# IotaWatt5_1.net
KiCad netlist of a schematic drawn in EAGLE
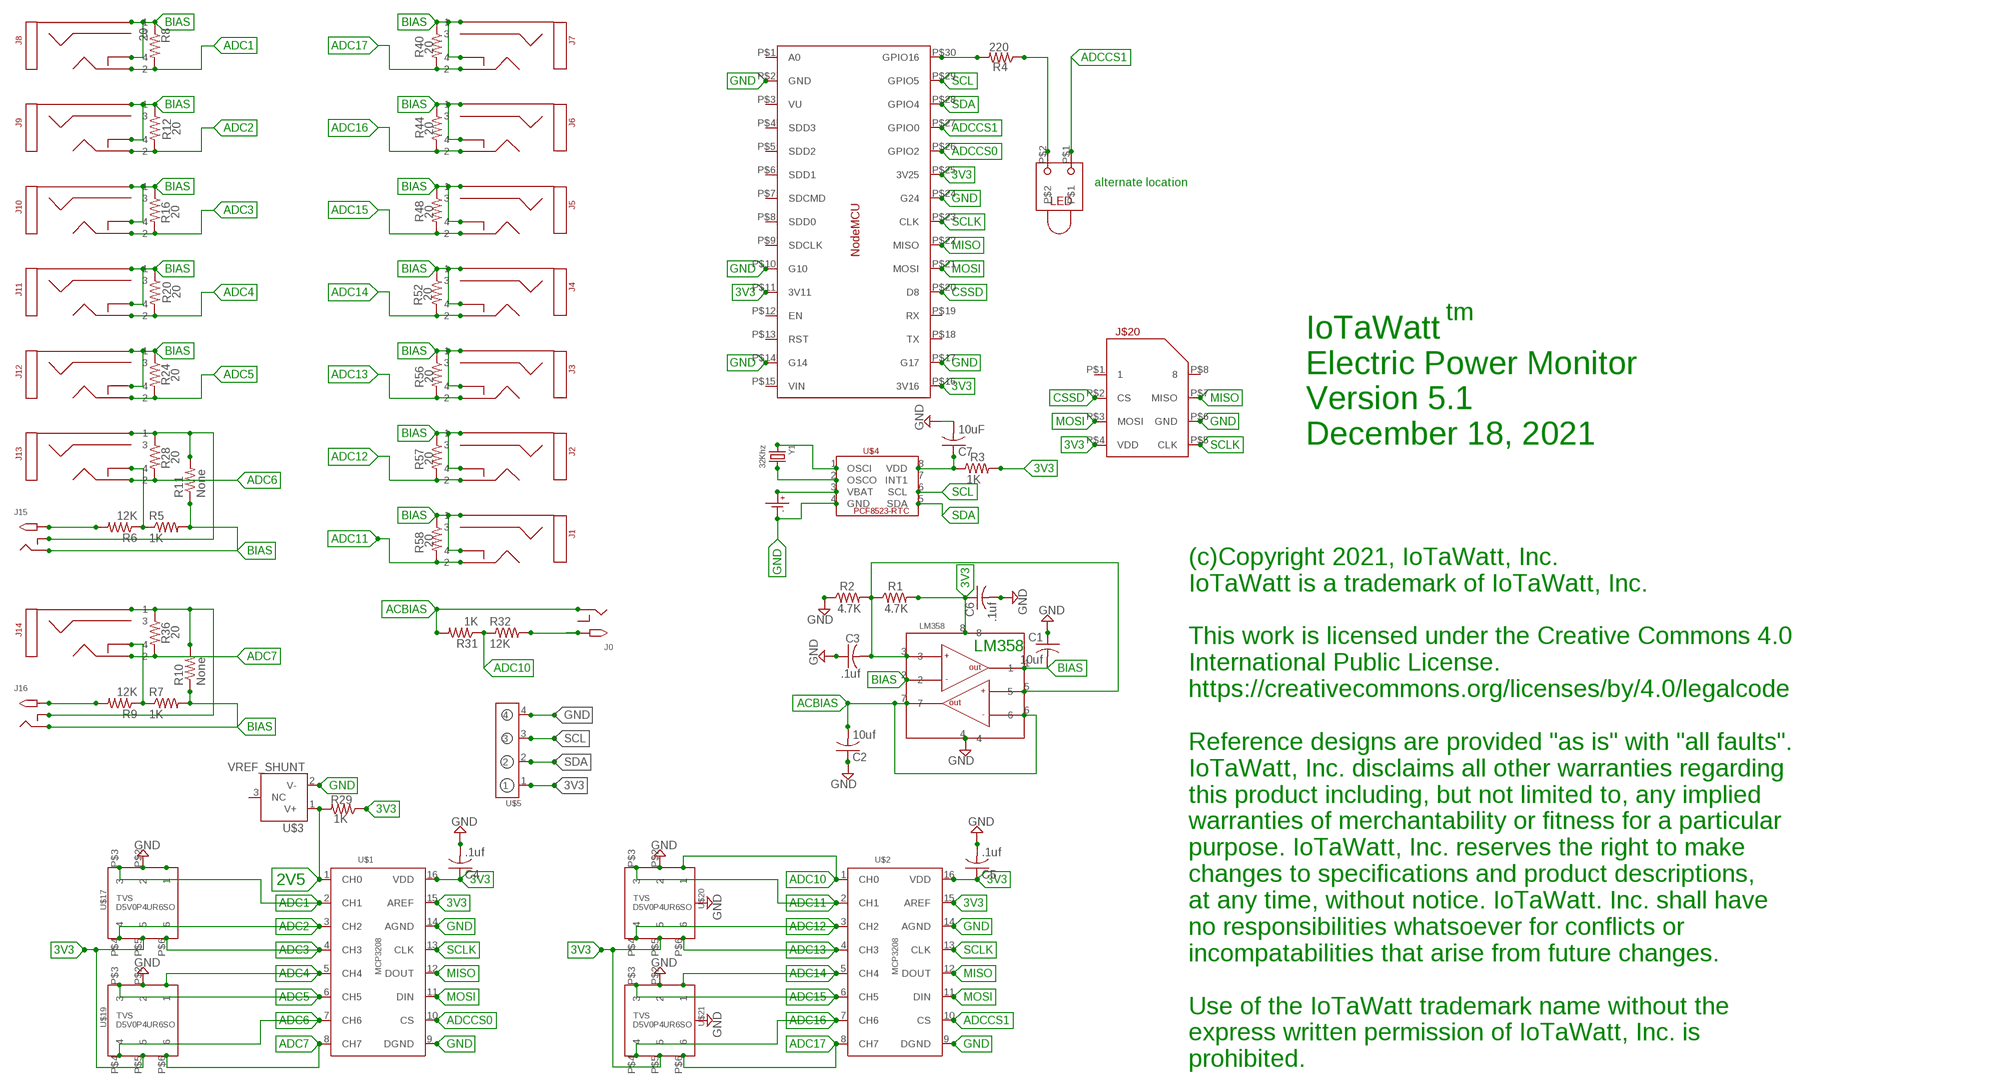
[diagram p0: schematic, sheet 1]

(export (version "E")
  (design (tool "Eeschema 10.0.6"))
  (components
    (comp (ref "C1")
      (value "10uf")
      (footprint "eagle-import:C0805")
      (libsource (lib "eagle-import") (part "C-USC0805"))
    )
    (comp (ref "C2")
      (value "10uf")
      (footprint "eagle-import:C0805")
      (libsource (lib "eagle-import") (part "C-USC0805"))
    )
    (comp (ref "C3")
      (value ".1uf")
      (footprint "eagle-import:C0805")
      (libsource (lib "eagle-import") (part "C-USC0805"))
    )
    (comp (ref "C4")
      (value ".1uf")
      (footprint "eagle-import:C0805")
      (libsource (lib "eagle-import") (part "C-USC0805"))
    )
    (comp (ref "C5")
      (value ".1uf")
      (footprint "eagle-import:C0805")
      (libsource (lib "eagle-import") (part "C-USC0805"))
    )
    (comp (ref "C6")
      (value ".1uf")
      (footprint "eagle-import:C0805")
      (libsource (lib "eagle-import") (part "C-USC0805"))
    )
    (comp (ref "C7")
      (value "10uF")
      (footprint "eagle-import:C0805")
      (libsource (lib "eagle-import") (part "C-USC0805"))
    )
    (comp (ref "J$20")
      (value "MICROSD_PUSH/PULL")
      (footprint "eagle-import:MICROSD")
      (libsource (lib "eagle-import") (part "MICROSD_PUSH/PULL"))
    )
    (comp (ref "J0")
      (value "2.1MMJACKSMT")
      (footprint "eagle-import:DCJACK_2MM_SMT")
      (libsource (lib "eagle-import") (part "2.1MMJACKSMT"))
    )
    (comp (ref "J1")
      (value "STEREO_SMD")
      (footprint "eagle-import:STEREO_SMT")
      (libsource (lib "eagle-import") (part "STEREO_SMD"))
    )
    (comp (ref "J2")
      (value "STEREO_SMD")
      (footprint "eagle-import:STEREO_SMT")
      (libsource (lib "eagle-import") (part "STEREO_SMD"))
    )
    (comp (ref "J3")
      (value "STEREO_SMD")
      (footprint "eagle-import:STEREO_SMT")
      (libsource (lib "eagle-import") (part "STEREO_SMD"))
    )
    (comp (ref "J4")
      (value "STEREO_SMD")
      (footprint "eagle-import:STEREO_SMT")
      (libsource (lib "eagle-import") (part "STEREO_SMD"))
    )
    (comp (ref "J5")
      (value "STEREO_SMD")
      (footprint "eagle-import:STEREO_SMT")
      (libsource (lib "eagle-import") (part "STEREO_SMD"))
    )
    (comp (ref "J6")
      (value "STEREO_SMD")
      (footprint "eagle-import:STEREO_SMT")
      (libsource (lib "eagle-import") (part "STEREO_SMD"))
    )
    (comp (ref "J7")
      (value "STEREO_SMD")
      (footprint "eagle-import:STEREO_SMT")
      (libsource (lib "eagle-import") (part "STEREO_SMD"))
    )
    (comp (ref "J8")
      (value "STEREO_SMD")
      (footprint "eagle-import:STEREO_SMT")
      (libsource (lib "eagle-import") (part "STEREO_SMD"))
    )
    (comp (ref "J9")
      (value "STEREO_SMD")
      (footprint "eagle-import:STEREO_SMT")
      (libsource (lib "eagle-import") (part "STEREO_SMD"))
    )
    (comp (ref "J10")
      (value "STEREO_SMD")
      (footprint "eagle-import:STEREO_SMT")
      (libsource (lib "eagle-import") (part "STEREO_SMD"))
    )
    (comp (ref "J11")
      (value "STEREO_SMD")
      (footprint "eagle-import:STEREO_SMT")
      (libsource (lib "eagle-import") (part "STEREO_SMD"))
    )
    (comp (ref "J12")
      (value "STEREO_SMD")
      (footprint "eagle-import:STEREO_SMT")
      (libsource (lib "eagle-import") (part "STEREO_SMD"))
    )
    (comp (ref "J13")
      (value "STEREO_SMD")
      (footprint "eagle-import:STEREO_SMT")
      (libsource (lib "eagle-import") (part "STEREO_SMD"))
    )
    (comp (ref "J14")
      (value "STEREO_SMD")
      (footprint "eagle-import:STEREO_SMT")
      (libsource (lib "eagle-import") (part "STEREO_SMD"))
    )
    (comp (ref "J15")
      (value "2.1MMJACKSMT")
      (footprint "eagle-import:DCJACK_2MM_SMT")
      (libsource (lib "eagle-import") (part "2.1MMJACKSMT"))
    )
    (comp (ref "J16")
      (value "2.1MMJACKSMT")
      (footprint "eagle-import:DCJACK_2MM_SMT")
      (libsource (lib "eagle-import") (part "2.1MMJACKSMT"))
    )
    (comp (ref "R1")
      (value "4.7K")
      (footprint "eagle-import:R0805")
      (libsource (lib "eagle-import") (part "R-US_R0805"))
    )
    (comp (ref "R2")
      (value "4.7K")
      (footprint "eagle-import:R0805")
      (libsource (lib "eagle-import") (part "R-US_R0805"))
    )
    (comp (ref "R3")
      (value "1K")
      (footprint "eagle-import:R0805")
      (libsource (lib "eagle-import") (part "R-US_R0805"))
    )
    (comp (ref "R4")
      (value "220")
      (footprint "eagle-import:R0805")
      (libsource (lib "eagle-import") (part "R-US_R0805"))
    )
    (comp (ref "R5")
      (value "1K")
      (footprint "eagle-import:R0805")
      (libsource (lib "eagle-import") (part "R-US_R0805"))
    )
    (comp (ref "R6")
      (value "12K")
      (footprint "eagle-import:R0805")
      (libsource (lib "eagle-import") (part "R-US_R0805"))
    )
    (comp (ref "R7")
      (value "1K")
      (footprint "eagle-import:R0805")
      (libsource (lib "eagle-import") (part "R-US_R0805"))
    )
    (comp (ref "R8")
      (value "20")
      (footprint "eagle-import:R0805")
      (libsource (lib "eagle-import") (part "R-US_R0805"))
    )
    (comp (ref "R9")
      (value "12K")
      (footprint "eagle-import:R0805")
      (libsource (lib "eagle-import") (part "R-US_R0805"))
    )
    (comp (ref "R10")
      (value "None")
      (footprint "eagle-import:R0805")
      (libsource (lib "eagle-import") (part "R-US_R0805"))
    )
    (comp (ref "R11")
      (value "None")
      (footprint "eagle-import:R0805")
      (libsource (lib "eagle-import") (part "R-US_R0805"))
    )
    (comp (ref "R12")
      (value "20")
      (footprint "eagle-import:R0805")
      (libsource (lib "eagle-import") (part "R-US_R0805"))
    )
    (comp (ref "R16")
      (value "20")
      (footprint "eagle-import:R0805")
      (libsource (lib "eagle-import") (part "R-US_R0805"))
    )
    (comp (ref "R20")
      (value "20")
      (footprint "eagle-import:R0805")
      (libsource (lib "eagle-import") (part "R-US_R0805"))
    )
    (comp (ref "R24")
      (value "20")
      (footprint "eagle-import:R0805")
      (libsource (lib "eagle-import") (part "R-US_R0805"))
    )
    (comp (ref "R28")
      (value "20")
      (footprint "eagle-import:R0805")
      (libsource (lib "eagle-import") (part "R-US_R0805"))
    )
    (comp (ref "R29")
      (value "1K")
      (footprint "eagle-import:R0805")
      (libsource (lib "eagle-import") (part "R-US_R0805"))
    )
    (comp (ref "R31")
      (value "1K")
      (footprint "eagle-import:R0805")
      (libsource (lib "eagle-import") (part "R-US_R0805"))
    )
    (comp (ref "R32")
      (value "12K")
      (footprint "eagle-import:R0805")
      (libsource (lib "eagle-import") (part "R-US_R0805"))
    )
    (comp (ref "R36")
      (value "20")
      (footprint "eagle-import:R0805")
      (libsource (lib "eagle-import") (part "R-US_R0805"))
    )
    (comp (ref "R40")
      (value "20")
      (footprint "eagle-import:R0805")
      (libsource (lib "eagle-import") (part "R-US_R0805"))
    )
    (comp (ref "R44")
      (value "20")
      (footprint "eagle-import:R0805")
      (libsource (lib "eagle-import") (part "R-US_R0805"))
    )
    (comp (ref "R48")
      (value "20")
      (footprint "eagle-import:R0805")
      (libsource (lib "eagle-import") (part "R-US_R0805"))
    )
    (comp (ref "R52")
      (value "20")
      (footprint "eagle-import:R0805")
      (libsource (lib "eagle-import") (part "R-US_R0805"))
    )
    (comp (ref "R56")
      (value "20")
      (footprint "eagle-import:R0805")
      (libsource (lib "eagle-import") (part "R-US_R0805"))
    )
    (comp (ref "R57")
      (value "20")
      (footprint "eagle-import:R0805")
      (libsource (lib "eagle-import") (part "R-US_R0805"))
    )
    (comp (ref "R58")
      (value "20")
      (footprint "eagle-import:R0805")
      (libsource (lib "eagle-import") (part "R-US_R0805"))
    )
    (comp (ref "U$1")
      (value "MCP3208")
      (footprint "eagle-import:SOIC_16")
      (libsource (lib "eagle-import") (part "MCP3208"))
    )
    (comp (ref "U$2")
      (value "MCP3208")
      (footprint "eagle-import:SOIC_16")
      (libsource (lib "eagle-import") (part "MCP3208"))
    )
    (comp (ref "U$3")
      (value "VREF_SHUNT")
      (footprint "eagle-import:SOT23_3")
      (libsource (lib "eagle-import") (part "VREF_SHUNT"))
    )
    (comp (ref "U$4")
      (value "PCF8523_RTC")
      (footprint "eagle-import:SOIC_8")
      (libsource (lib "eagle-import") (part "PCF8523_RTC"))
    )
    (comp (ref "U$5")
      (value "HEADER_1X4")
      (footprint "eagle-import:HEADER_1X4")
      (libsource (lib "eagle-import") (part "HEADER_1X4"))
    )
    (comp (ref "U$16")
      (value "NODEMCU")
      (footprint "eagle-import:NODEMCU")
      (libsource (lib "eagle-import") (part "NODEMCU"))
    )
    (comp (ref "U$17")
      (value "TVS_4CHAN_ARRAYSC-74")
      (footprint "eagle-import:SC-74")
      (libsource (lib "eagle-import") (part "TVS_4CHAN_ARRAYSC-74"))
    )
    (comp (ref "U$18")
      (value "CR1220SMD")
      (footprint "eagle-import:CR1220SMD")
      (libsource (lib "eagle-import") (part "CR1220SMD"))
    )
    (comp (ref "U$19")
      (value "TVS_4CHAN_ARRAYSC-74")
      (footprint "eagle-import:SC-74")
      (libsource (lib "eagle-import") (part "TVS_4CHAN_ARRAYSC-74"))
    )
    (comp (ref "U$20")
      (value "TVS_4CHAN_ARRAYSC-74")
      (footprint "eagle-import:SC-74")
      (libsource (lib "eagle-import") (part "TVS_4CHAN_ARRAYSC-74"))
    )
    (comp (ref "U$21")
      (value "TVS_4CHAN_ARRAYSC-74")
      (footprint "eagle-import:SC-74")
      (libsource (lib "eagle-import") (part "TVS_4CHAN_ARRAYSC-74"))
    )
    (comp (ref "U$22")
      (value "LM358_DUAL_OP-AMP")
      (footprint "eagle-import:SOIC_8")
      (libsource (lib "eagle-import") (part "LM358_DUAL_OP-AMP"))
    )
    (comp (ref "U$23")
      (value "LED_RT_TRH")
      (footprint "eagle-import:LED_TH_RT")
      (libsource (lib "eagle-import") (part "LED_RT_TRH"))
    )
    (comp (ref "Y1")
      (value "32Khz")
      (footprint "eagle-import:CRYSTAL_8X3.8")
      (libsource (lib "eagle-import") (part "CRYSTAL8X3.8SMT"))
    )
  )
  (nets
    (net (code "1") (name "2V5") (class "Default")
      (node (ref "R29") (pin "2") (pinfunction "2_2") (pintype "passive"))
      (node (ref "U$1") (pin "1") (pinfunction "CH0_1") (pintype "input"))
      (node (ref "U$3") (pin "1") (pinfunction "V+_1") (pintype "bidirectional"))
    )
    (net (code "2") (name "3V3") (class "Default")
      (node (ref "C4") (pin "1") (pinfunction "1_1") (pintype "passive"))
      (node (ref "C5") (pin "1") (pinfunction "1_1") (pintype "passive"))
      (node (ref "C6") (pin "1") (pinfunction "1_1") (pintype "passive"))
      (node (ref "J$20") (pin "P$4") (pinfunction "VDD_P$4") (pintype "bidirectional"))
      (node (ref "R1") (pin "2") (pinfunction "2_2") (pintype "passive"))
      (node (ref "R29") (pin "1") (pinfunction "1_1") (pintype "passive"))
      (node (ref "R3") (pin "2") (pinfunction "2_2") (pintype "passive"))
      (node (ref "U$1") (pin "15") (pinfunction "AREF_15") (pintype "input"))
      (node (ref "U$1") (pin "16") (pinfunction "VDD_16") (pintype "bidirectional"))
      (node (ref "U$16") (pin "P$11") (pinfunction "3V11_P$11") (pintype "bidirectional"))
      (node (ref "U$16") (pin "P$16") (pinfunction "3V16_P$16") (pintype "bidirectional"))
      (node (ref "U$16") (pin "P$25") (pinfunction "3V25_P$25") (pintype "bidirectional"))
      (node (ref "U$17") (pin "P$5") (pinfunction "5_P$5") (pintype "bidirectional"))
      (node (ref "U$19") (pin "P$5") (pinfunction "5_P$5") (pintype "bidirectional"))
      (node (ref "U$2") (pin "15") (pinfunction "AREF_15") (pintype "input"))
      (node (ref "U$2") (pin "16") (pinfunction "VDD_16") (pintype "bidirectional"))
      (node (ref "U$20") (pin "P$5") (pinfunction "5_P$5") (pintype "bidirectional"))
      (node (ref "U$21") (pin "P$5") (pinfunction "5_P$5") (pintype "bidirectional"))
      (node (ref "U$22") (pin "8") (pinfunction "8_8") (pintype "bidirectional"))
      (node (ref "U$5") (pin "1") (pinfunction "1_1") (pintype "bidirectional"))
    )
    (net (code "3") (name "ACBIAS") (class "Default")
      (node (ref "C2") (pin "2") (pinfunction "2_2") (pintype "passive"))
      (node (ref "J0") (pin "GND") (pinfunction "RING_GND") (pintype "bidirectional"))
      (node (ref "R31") (pin "2") (pinfunction "2_2") (pintype "passive"))
      (node (ref "U$22") (pin "6") (pinfunction "6_6") (pintype "bidirectional"))
      (node (ref "U$22") (pin "7") (pinfunction "7_7") (pintype "bidirectional"))
    )
    (net (code "4") (name "ADC1") (class "Default")
      (node (ref "J8") (pin "P$2") (pinfunction "2_P$2") (pintype "bidirectional"))
      (node (ref "R8") (pin "2") (pinfunction "2_2") (pintype "passive"))
      (node (ref "U$1") (pin "2") (pinfunction "CH1_2") (pintype "input"))
      (node (ref "U$17") (pin "P$3") (pinfunction "3_P$3") (pintype "bidirectional"))
    )
    (net (code "5") (name "ADC2") (class "Default")
      (node (ref "J9") (pin "P$2") (pinfunction "2_P$2") (pintype "bidirectional"))
      (node (ref "R12") (pin "2") (pinfunction "2_2") (pintype "passive"))
      (node (ref "U$1") (pin "3") (pinfunction "CH2_3") (pintype "input"))
      (node (ref "U$17") (pin "P$4") (pinfunction "4_P$4") (pintype "bidirectional"))
    )
    (net (code "6") (name "ADC3") (class "Default")
      (node (ref "J10") (pin "P$2") (pinfunction "2_P$2") (pintype "bidirectional"))
      (node (ref "R16") (pin "2") (pinfunction "2_2") (pintype "passive"))
      (node (ref "U$1") (pin "4") (pinfunction "CH3_4") (pintype "input"))
      (node (ref "U$17") (pin "P$6") (pinfunction "6_P$6") (pintype "bidirectional"))
    )
    (net (code "7") (name "ADC4") (class "Default")
      (node (ref "J11") (pin "P$2") (pinfunction "2_P$2") (pintype "bidirectional"))
      (node (ref "R20") (pin "2") (pinfunction "2_2") (pintype "passive"))
      (node (ref "U$1") (pin "5") (pinfunction "CH4_5") (pintype "bidirectional"))
      (node (ref "U$19") (pin "P$1") (pinfunction "1_P$1") (pintype "bidirectional"))
    )
    (net (code "8") (name "ADC5") (class "Default")
      (node (ref "J12") (pin "P$2") (pinfunction "2_P$2") (pintype "bidirectional"))
      (node (ref "R24") (pin "2") (pinfunction "2_2") (pintype "passive"))
      (node (ref "U$1") (pin "6") (pinfunction "CH5_6") (pintype "bidirectional"))
      (node (ref "U$19") (pin "P$3") (pinfunction "3_P$3") (pintype "bidirectional"))
    )
    (net (code "9") (name "ADC6") (class "Default")
      (node (ref "J13") (pin "P$2") (pinfunction "2_P$2") (pintype "bidirectional"))
      (node (ref "R28") (pin "2") (pinfunction "2_2") (pintype "passive"))
      (node (ref "U$1") (pin "7") (pinfunction "CH6_7") (pintype "input"))
      (node (ref "U$19") (pin "P$4") (pinfunction "4_P$4") (pintype "bidirectional"))
    )
    (net (code "10") (name "ADC7") (class "Default")
      (node (ref "J14") (pin "P$2") (pinfunction "2_P$2") (pintype "bidirectional"))
      (node (ref "R36") (pin "2") (pinfunction "2_2") (pintype "passive"))
      (node (ref "U$1") (pin "8") (pinfunction "CH7_8") (pintype "bidirectional"))
      (node (ref "U$19") (pin "P$6") (pinfunction "6_P$6") (pintype "bidirectional"))
    )
    (net (code "11") (name "ADC10") (class "Default")
      (node (ref "R31") (pin "1") (pinfunction "1_1") (pintype "passive"))
      (node (ref "R32") (pin "1") (pinfunction "1_1") (pintype "passive"))
      (node (ref "U$2") (pin "1") (pinfunction "CH0_1") (pintype "input"))
      (node (ref "U$20") (pin "P$1") (pinfunction "1_P$1") (pintype "bidirectional"))
    )
    (net (code "12") (name "ADC11") (class "Default")
      (node (ref "J1") (pin "P$2") (pinfunction "2_P$2") (pintype "bidirectional"))
      (node (ref "R58") (pin "2") (pinfunction "2_2") (pintype "passive"))
      (node (ref "U$2") (pin "2") (pinfunction "CH1_2") (pintype "input"))
      (node (ref "U$20") (pin "P$3") (pinfunction "3_P$3") (pintype "bidirectional"))
    )
    (net (code "13") (name "ADC12") (class "Default")
      (node (ref "J2") (pin "P$2") (pinfunction "2_P$2") (pintype "bidirectional"))
      (node (ref "R57") (pin "2") (pinfunction "2_2") (pintype "passive"))
      (node (ref "U$2") (pin "3") (pinfunction "CH2_3") (pintype "input"))
      (node (ref "U$20") (pin "P$4") (pinfunction "4_P$4") (pintype "bidirectional"))
    )
    (net (code "14") (name "ADC13") (class "Default")
      (node (ref "J3") (pin "P$2") (pinfunction "2_P$2") (pintype "bidirectional"))
      (node (ref "R56") (pin "2") (pinfunction "2_2") (pintype "passive"))
      (node (ref "U$2") (pin "4") (pinfunction "CH3_4") (pintype "input"))
      (node (ref "U$20") (pin "P$6") (pinfunction "6_P$6") (pintype "bidirectional"))
    )
    (net (code "15") (name "ADC14") (class "Default")
      (node (ref "J4") (pin "P$2") (pinfunction "2_P$2") (pintype "bidirectional"))
      (node (ref "R52") (pin "2") (pinfunction "2_2") (pintype "passive"))
      (node (ref "U$2") (pin "5") (pinfunction "CH4_5") (pintype "bidirectional"))
      (node (ref "U$21") (pin "P$1") (pinfunction "1_P$1") (pintype "bidirectional"))
    )
    (net (code "16") (name "ADC15") (class "Default")
      (node (ref "J5") (pin "P$2") (pinfunction "2_P$2") (pintype "bidirectional"))
      (node (ref "R48") (pin "2") (pinfunction "2_2") (pintype "passive"))
      (node (ref "U$2") (pin "6") (pinfunction "CH5_6") (pintype "bidirectional"))
      (node (ref "U$21") (pin "P$3") (pinfunction "3_P$3") (pintype "bidirectional"))
    )
    (net (code "17") (name "ADC16") (class "Default")
      (node (ref "J6") (pin "P$2") (pinfunction "2_P$2") (pintype "bidirectional"))
      (node (ref "R44") (pin "2") (pinfunction "2_2") (pintype "passive"))
      (node (ref "U$2") (pin "7") (pinfunction "CH6_7") (pintype "input"))
      (node (ref "U$21") (pin "P$4") (pinfunction "4_P$4") (pintype "bidirectional"))
    )
    (net (code "18") (name "ADC17") (class "Default")
      (node (ref "J7") (pin "P$2") (pinfunction "2_P$2") (pintype "bidirectional"))
      (node (ref "R40") (pin "2") (pinfunction "2_2") (pintype "passive"))
      (node (ref "U$2") (pin "8") (pinfunction "CH7_8") (pintype "bidirectional"))
      (node (ref "U$21") (pin "P$6") (pinfunction "6_P$6") (pintype "bidirectional"))
    )
    (net (code "19") (name "ADCCS0") (class "Default")
      (node (ref "U$1") (pin "10") (pinfunction "CS_10") (pintype "input"))
      (node (ref "U$16") (pin "P$26") (pinfunction "GPIO2_P$26") (pintype "bidirectional"))
    )
    (net (code "20") (name "ADCCS1") (class "Default")
      (node (ref "U$16") (pin "P$27") (pinfunction "GPIO0_P$27") (pintype "bidirectional"))
      (node (ref "U$2") (pin "10") (pinfunction "CS_10") (pintype "input"))
      (node (ref "U$23") (pin "P$1") (pinfunction "P$1_P$1") (pintype "bidirectional"))
    )
    (net (code "21") (name "BIAS") (class "Default")
      (node (ref "C1") (pin "2") (pinfunction "2_2") (pintype "passive"))
      (node (ref "J1") (pin "P$1") (pinfunction "1_P$1") (pintype "bidirectional"))
      (node (ref "J1") (pin "P$4") (pinfunction "4_P$4") (pintype "bidirectional"))
      (node (ref "J10") (pin "P$1") (pinfunction "1_P$1") (pintype "bidirectional"))
      (node (ref "J10") (pin "P$4") (pinfunction "4_P$4") (pintype "bidirectional"))
      (node (ref "J11") (pin "P$1") (pinfunction "1_P$1") (pintype "bidirectional"))
      (node (ref "J11") (pin "P$4") (pinfunction "4_P$4") (pintype "bidirectional"))
      (node (ref "J12") (pin "P$1") (pinfunction "1_P$1") (pintype "bidirectional"))
      (node (ref "J12") (pin "P$4") (pinfunction "4_P$4") (pintype "bidirectional"))
      (node (ref "J15") (pin "GND") (pinfunction "RING_GND") (pintype "bidirectional"))
      (node (ref "J16") (pin "GND") (pinfunction "RING_GND") (pintype "bidirectional"))
      (node (ref "J2") (pin "P$1") (pinfunction "1_P$1") (pintype "bidirectional"))
      (node (ref "J2") (pin "P$4") (pinfunction "4_P$4") (pintype "bidirectional"))
      (node (ref "J3") (pin "P$1") (pinfunction "1_P$1") (pintype "bidirectional"))
      (node (ref "J3") (pin "P$4") (pinfunction "4_P$4") (pintype "bidirectional"))
      (node (ref "J4") (pin "P$1") (pinfunction "1_P$1") (pintype "bidirectional"))
      (node (ref "J4") (pin "P$4") (pinfunction "4_P$4") (pintype "bidirectional"))
      (node (ref "J5") (pin "P$1") (pinfunction "1_P$1") (pintype "bidirectional"))
      (node (ref "J5") (pin "P$4") (pinfunction "4_P$4") (pintype "bidirectional"))
      (node (ref "J6") (pin "P$1") (pinfunction "1_P$1") (pintype "bidirectional"))
      (node (ref "J6") (pin "P$4") (pinfunction "4_P$4") (pintype "bidirectional"))
      (node (ref "J7") (pin "P$1") (pinfunction "1_P$1") (pintype "bidirectional"))
      (node (ref "J7") (pin "P$4") (pinfunction "4_P$4") (pintype "bidirectional"))
      (node (ref "J8") (pin "P$1") (pinfunction "1_P$1") (pintype "bidirectional"))
      (node (ref "J8") (pin "P$4") (pinfunction "4_P$4") (pintype "bidirectional"))
      (node (ref "J9") (pin "P$1") (pinfunction "1_P$1") (pintype "bidirectional"))
      (node (ref "J9") (pin "P$4") (pinfunction "4_P$4") (pintype "bidirectional"))
      (node (ref "R10") (pin "1") (pinfunction "1_1") (pintype "passive"))
      (node (ref "R11") (pin "1") (pinfunction "1_1") (pintype "passive"))
      (node (ref "R12") (pin "1") (pinfunction "1_1") (pintype "passive"))
      (node (ref "R16") (pin "1") (pinfunction "1_1") (pintype "passive"))
      (node (ref "R20") (pin "1") (pinfunction "1_1") (pintype "passive"))
      (node (ref "R24") (pin "1") (pinfunction "1_1") (pintype "passive"))
      (node (ref "R40") (pin "1") (pinfunction "1_1") (pintype "passive"))
      (node (ref "R44") (pin "1") (pinfunction "1_1") (pintype "passive"))
      (node (ref "R48") (pin "1") (pinfunction "1_1") (pintype "passive"))
      (node (ref "R5") (pin "2") (pinfunction "2_2") (pintype "passive"))
      (node (ref "R52") (pin "1") (pinfunction "1_1") (pintype "passive"))
      (node (ref "R56") (pin "1") (pinfunction "1_1") (pintype "passive"))
      (node (ref "R57") (pin "1") (pinfunction "1_1") (pintype "passive"))
      (node (ref "R58") (pin "1") (pinfunction "1_1") (pintype "passive"))
      (node (ref "R7") (pin "2") (pinfunction "2_2") (pintype "passive"))
      (node (ref "R8") (pin "1") (pinfunction "1_1") (pintype "passive"))
      (node (ref "U$22") (pin "1") (pinfunction "1_1") (pintype "bidirectional"))
      (node (ref "U$22") (pin "2") (pinfunction "2_2") (pintype "bidirectional"))
    )
    (net (code "22") (name "CSSD") (class "Default")
      (node (ref "J$20") (pin "P$2") (pinfunction "CS_P$2") (pintype "bidirectional"))
      (node (ref "U$16") (pin "P$20") (pinfunction "D8_P$20") (pintype "bidirectional"))
    )
    (net (code "23") (name "GND") (class "Default")
      (node (ref "C1") (pin "1") (pinfunction "1_1") (pintype "passive"))
      (node (ref "C2") (pin "1") (pinfunction "1_1") (pintype "passive"))
      (node (ref "C3") (pin "1") (pinfunction "1_1") (pintype "passive"))
      (node (ref "C4") (pin "2") (pinfunction "2_2") (pintype "passive"))
      (node (ref "C5") (pin "2") (pinfunction "2_2") (pintype "passive"))
      (node (ref "C6") (pin "2") (pinfunction "2_2") (pintype "passive"))
      (node (ref "C7") (pin "2") (pinfunction "2_2") (pintype "passive"))
      (node (ref "J$20") (pin "P$6") (pinfunction "GND_P$6") (pintype "bidirectional"))
      (node (ref "R2") (pin "1") (pinfunction "1_1") (pintype "passive"))
      (node (ref "U$1") (pin "14") (pinfunction "AGND_14") (pintype "input"))
      (node (ref "U$1") (pin "9") (pinfunction "DGND_9") (pintype "bidirectional"))
      (node (ref "U$16") (pin "P$10") (pinfunction "G10_P$10") (pintype "bidirectional"))
      (node (ref "U$16") (pin "P$14") (pinfunction "G14_P$14") (pintype "bidirectional"))
      (node (ref "U$16") (pin "P$17") (pinfunction "G17_P$17") (pintype "bidirectional"))
      (node (ref "U$16") (pin "P$2") (pinfunction "GND_P$2") (pintype "bidirectional"))
      (node (ref "U$16") (pin "P$24") (pinfunction "G24_P$24") (pintype "bidirectional"))
      (node (ref "U$17") (pin "P$2") (pinfunction "2_P$2") (pintype "bidirectional"))
      (node (ref "U$18") (pin "P-") (pinfunction "P$-_P-") (pintype "bidirectional"))
      (node (ref "U$19") (pin "P$2") (pinfunction "2_P$2") (pintype "bidirectional"))
      (node (ref "U$2") (pin "14") (pinfunction "AGND_14") (pintype "input"))
      (node (ref "U$2") (pin "9") (pinfunction "DGND_9") (pintype "bidirectional"))
      (node (ref "U$20") (pin "P$2") (pinfunction "2_P$2") (pintype "bidirectional"))
      (node (ref "U$21") (pin "P$2") (pinfunction "2_P$2") (pintype "bidirectional"))
      (node (ref "U$22") (pin "4") (pinfunction "4_4") (pintype "bidirectional"))
      (node (ref "U$3") (pin "2") (pinfunction "V-_2") (pintype "bidirectional"))
      (node (ref "U$4") (pin "4") (pinfunction "GND_4") (pintype "bidirectional"))
      (node (ref "U$5") (pin "4") (pinfunction "4_4") (pintype "bidirectional"))
    )
    (net (code "24") (name "MISO") (class "Default")
      (node (ref "J$20") (pin "P$7") (pinfunction "MISO_P$7") (pintype "bidirectional"))
      (node (ref "U$1") (pin "12") (pinfunction "DOUT_12") (pintype "bidirectional"))
      (node (ref "U$16") (pin "P$22") (pinfunction "MISO_P$22") (pintype "bidirectional"))
      (node (ref "U$2") (pin "12") (pinfunction "DOUT_12") (pintype "bidirectional"))
    )
    (net (code "25") (name "MOSI") (class "Default")
      (node (ref "J$20") (pin "P$3") (pinfunction "MOSI_P$3") (pintype "bidirectional"))
      (node (ref "U$1") (pin "11") (pinfunction "DIN_11") (pintype "input"))
      (node (ref "U$16") (pin "P$21") (pinfunction "MOSI_P$21") (pintype "bidirectional"))
      (node (ref "U$2") (pin "11") (pinfunction "DIN_11") (pintype "input"))
    )
    (net (code "26") (name "Net-(C3-Pad2)") (class "Default")
      (node (ref "C3") (pin "2") (pinfunction "2_2") (pintype "passive"))
      (node (ref "R1") (pin "1") (pinfunction "1_1") (pintype "passive"))
      (node (ref "R2") (pin "2") (pinfunction "2_2") (pintype "passive"))
      (node (ref "U$22") (pin "3") (pinfunction "3_3") (pintype "bidirectional"))
      (node (ref "U$22") (pin "5") (pinfunction "5_5") (pintype "bidirectional"))
    )
    (net (code "27") (name "Net-(J0-TIP)") (class "Default")
      (node (ref "J0") (pin "PWR2") (pinfunction "TIP_PWR2") (pintype "bidirectional"))
      (node (ref "R32") (pin "2") (pinfunction "2_2") (pintype "passive"))
    )
    (net (code "28") (name "Net-(J13-1)") (class "Default")
      (node (ref "J13") (pin "P$1") (pinfunction "1_P$1") (pintype "bidirectional"))
      (node (ref "J15") (pin "GNDBREAK") (pinfunction "RING_SW_GNDBREAK") (pintype "bidirectional"))
      (node (ref "R11") (pin "2") (pinfunction "2_2") (pintype "passive"))
      (node (ref "R28") (pin "1") (pinfunction "1_1") (pintype "passive"))
    )
    (net (code "29") (name "Net-(J13-4)") (class "Default")
      (node (ref "J13") (pin "P$4") (pinfunction "4_P$4") (pintype "bidirectional"))
      (node (ref "R5") (pin "1") (pinfunction "1_1") (pintype "passive"))
      (node (ref "R6") (pin "1") (pinfunction "1_1") (pintype "passive"))
    )
    (net (code "30") (name "Net-(J14-1)") (class "Default")
      (node (ref "J14") (pin "P$1") (pinfunction "1_P$1") (pintype "bidirectional"))
      (node (ref "J16") (pin "GNDBREAK") (pinfunction "RING_SW_GNDBREAK") (pintype "bidirectional"))
      (node (ref "R10") (pin "2") (pinfunction "2_2") (pintype "passive"))
      (node (ref "R36") (pin "1") (pinfunction "1_1") (pintype "passive"))
    )
    (net (code "31") (name "Net-(J14-4)") (class "Default")
      (node (ref "J14") (pin "P$4") (pinfunction "4_P$4") (pintype "bidirectional"))
      (node (ref "R7") (pin "1") (pinfunction "1_1") (pintype "passive"))
      (node (ref "R9") (pin "1") (pinfunction "1_1") (pintype "passive"))
    )
    (net (code "32") (name "Net-(J15-TIP)") (class "Default")
      (node (ref "J15") (pin "PWR2") (pinfunction "TIP_PWR2") (pintype "bidirectional"))
      (node (ref "R6") (pin "2") (pinfunction "2_2") (pintype "passive"))
    )
    (net (code "33") (name "Net-(J16-TIP)") (class "Default")
      (node (ref "J16") (pin "PWR2") (pinfunction "TIP_PWR2") (pintype "bidirectional"))
      (node (ref "R9") (pin "2") (pinfunction "2_2") (pintype "passive"))
    )
    (net (code "34") (name "Net-(R4-Pad1)") (class "Default")
      (node (ref "R4") (pin "1") (pinfunction "1_1") (pintype "passive"))
      (node (ref "U$23") (pin "P$2") (pinfunction "P$2_P$2") (pintype "bidirectional"))
    )
    (net (code "35") (name "Net-(U$4-OSCI)") (class "Default")
      (node (ref "U$4") (pin "1") (pinfunction "OSCI_1") (pintype "bidirectional"))
      (node (ref "Y1") (pin "P$1") (pinfunction "1_P$1") (pintype "passive"))
    )
    (net (code "36") (name "Net-(U$4-OSCO)") (class "Default")
      (node (ref "U$4") (pin "2") (pinfunction "OSCO_2") (pintype "bidirectional"))
      (node (ref "Y1") (pin "P$4") (pinfunction "2_P$4") (pintype "passive"))
    )
    (net (code "37") (name "Net-(U$4-VDD)") (class "Default")
      (node (ref "C7") (pin "1") (pinfunction "1_1") (pintype "passive"))
      (node (ref "R3") (pin "1") (pinfunction "1_1") (pintype "passive"))
      (node (ref "U$4") (pin "8") (pinfunction "VDD_8") (pintype "bidirectional"))
    )
    (net (code "38") (name "Net-(U$16-GPIO16)") (class "Default")
      (node (ref "R4") (pin "2") (pinfunction "2_2") (pintype "passive"))
      (node (ref "U$16") (pin "P$30") (pinfunction "GPIO16_P$30") (pintype "bidirectional"))
    )
    (net (code "39") (name "Net-(U$18-P$+)") (class "Default")
      (node (ref "U$18") (pin "P+") (pinfunction "P$+_P+") (pintype "bidirectional"))
      (node (ref "U$4") (pin "3") (pinfunction "VBAT_3") (pintype "bidirectional"))
    )
    (net (code "40") (name "SCL") (class "Default")
      (node (ref "U$16") (pin "P$29") (pinfunction "GPIO5_P$29") (pintype "bidirectional"))
      (node (ref "U$4") (pin "6") (pinfunction "SCL_6") (pintype "bidirectional"))
      (node (ref "U$5") (pin "3") (pinfunction "3_3") (pintype "bidirectional"))
    )
    (net (code "41") (name "SCLK") (class "Default")
      (node (ref "J$20") (pin "P$5") (pinfunction "CLK_P$5") (pintype "bidirectional"))
      (node (ref "U$1") (pin "13") (pinfunction "CLK_13") (pintype "input"))
      (node (ref "U$16") (pin "P$23") (pinfunction "CLK_P$23") (pintype "bidirectional"))
      (node (ref "U$2") (pin "13") (pinfunction "CLK_13") (pintype "input"))
    )
    (net (code "42") (name "SDA") (class "Default")
      (node (ref "U$16") (pin "P$28") (pinfunction "GPIO4_P$28") (pintype "bidirectional"))
      (node (ref "U$4") (pin "5") (pinfunction "SDA_5") (pintype "bidirectional"))
      (node (ref "U$5") (pin "2") (pinfunction "2_2") (pintype "bidirectional"))
    )
    (net (code "43") (name "unconnected-(J$20-1-PadP$1)") (class "Default")
      (node (ref "J$20") (pin "P$1") (pinfunction "1_P$1") (pintype "bidirectional"))
    )
    (net (code "44") (name "unconnected-(J$20-8-PadP$8)") (class "Default")
      (node (ref "J$20") (pin "P$8") (pinfunction "8_P$8") (pintype "bidirectional"))
    )
    (net (code "45") (name "unconnected-(J0-RING_SW-PadGNDBREAK)") (class "Default")
      (node (ref "J0") (pin "GNDBREAK") (pinfunction "RING_SW_GNDBREAK") (pintype "bidirectional"))
    )
    (net (code "46") (name "unconnected-(J1-3-PadP$3)") (class "Default")
      (node (ref "J1") (pin "P$3") (pinfunction "3_P$3") (pintype "bidirectional"))
    )
    (net (code "47") (name "unconnected-(J2-3-PadP$3)") (class "Default")
      (node (ref "J2") (pin "P$3") (pinfunction "3_P$3") (pintype "bidirectional"))
    )
    (net (code "48") (name "unconnected-(J3-3-PadP$3)") (class "Default")
      (node (ref "J3") (pin "P$3") (pinfunction "3_P$3") (pintype "bidirectional"))
    )
    (net (code "49") (name "unconnected-(J4-3-PadP$3)") (class "Default")
      (node (ref "J4") (pin "P$3") (pinfunction "3_P$3") (pintype "bidirectional"))
    )
    (net (code "50") (name "unconnected-(J5-3-PadP$3)") (class "Default")
      (node (ref "J5") (pin "P$3") (pinfunction "3_P$3") (pintype "bidirectional"))
    )
    (net (code "51") (name "unconnected-(J6-3-PadP$3)") (class "Default")
      (node (ref "J6") (pin "P$3") (pinfunction "3_P$3") (pintype "bidirectional"))
    )
    (net (code "52") (name "unconnected-(J7-3-PadP$3)") (class "Default")
      (node (ref "J7") (pin "P$3") (pinfunction "3_P$3") (pintype "bidirectional"))
    )
    (net (code "53") (name "unconnected-(J8-3-PadP$3)") (class "Default")
      (node (ref "J8") (pin "P$3") (pinfunction "3_P$3") (pintype "bidirectional"))
    )
    (net (code "54") (name "unconnected-(J9-3-PadP$3)") (class "Default")
      (node (ref "J9") (pin "P$3") (pinfunction "3_P$3") (pintype "bidirectional"))
    )
    (net (code "55") (name "unconnected-(J10-3-PadP$3)") (class "Default")
      (node (ref "J10") (pin "P$3") (pinfunction "3_P$3") (pintype "bidirectional"))
    )
    (net (code "56") (name "unconnected-(J11-3-PadP$3)") (class "Default")
      (node (ref "J11") (pin "P$3") (pinfunction "3_P$3") (pintype "bidirectional"))
    )
    (net (code "57") (name "unconnected-(J12-3-PadP$3)") (class "Default")
      (node (ref "J12") (pin "P$3") (pinfunction "3_P$3") (pintype "bidirectional"))
    )
    (net (code "58") (name "unconnected-(J13-3-PadP$3)") (class "Default")
      (node (ref "J13") (pin "P$3") (pinfunction "3_P$3") (pintype "bidirectional"))
    )
    (net (code "59") (name "unconnected-(J14-3-PadP$3)") (class "Default")
      (node (ref "J14") (pin "P$3") (pinfunction "3_P$3") (pintype "bidirectional"))
    )
    (net (code "60") (name "unconnected-(U$3-NC-Pad3)") (class "Default")
      (node (ref "U$3") (pin "3") (pinfunction "NC_3") (pintype "bidirectional"))
    )
    (net (code "61") (name "unconnected-(U$4-INT1-Pad7)") (class "Default")
      (node (ref "U$4") (pin "7") (pinfunction "INT1_7") (pintype "bidirectional"))
    )
    (net (code "62") (name "unconnected-(U$16-A0-PadP$1)") (class "Default")
      (node (ref "U$16") (pin "P$1") (pinfunction "A0_P$1") (pintype "bidirectional"))
    )
    (net (code "63") (name "unconnected-(U$16-EN-PadP$12)") (class "Default")
      (node (ref "U$16") (pin "P$12") (pinfunction "EN_P$12") (pintype "bidirectional"))
    )
    (net (code "64") (name "unconnected-(U$16-RST-PadP$13)") (class "Default")
      (node (ref "U$16") (pin "P$13") (pinfunction "RST_P$13") (pintype "bidirectional"))
    )
    (net (code "65") (name "unconnected-(U$16-RX-PadP$19)") (class "Default")
      (node (ref "U$16") (pin "P$19") (pinfunction "RX_P$19") (pintype "bidirectional"))
    )
    (net (code "66") (name "unconnected-(U$16-SDCLK-PadP$9)") (class "Default")
      (node (ref "U$16") (pin "P$9") (pinfunction "SDCLK_P$9") (pintype "bidirectional"))
    )
    (net (code "67") (name "unconnected-(U$16-SDCMD-PadP$7)") (class "Default")
      (node (ref "U$16") (pin "P$7") (pinfunction "SDCMD_P$7") (pintype "bidirectional"))
    )
    (net (code "68") (name "unconnected-(U$16-SDD0-PadP$8)") (class "Default")
      (node (ref "U$16") (pin "P$8") (pinfunction "SDD0_P$8") (pintype "bidirectional"))
    )
    (net (code "69") (name "unconnected-(U$16-SDD1-PadP$6)") (class "Default")
      (node (ref "U$16") (pin "P$6") (pinfunction "SDD1_P$6") (pintype "bidirectional"))
    )
    (net (code "70") (name "unconnected-(U$16-SDD2-PadP$5)") (class "Default")
      (node (ref "U$16") (pin "P$5") (pinfunction "SDD2_P$5") (pintype "bidirectional"))
    )
    (net (code "71") (name "unconnected-(U$16-SDD3-PadP$4)") (class "Default")
      (node (ref "U$16") (pin "P$4") (pinfunction "SDD3_P$4") (pintype "bidirectional"))
    )
    (net (code "72") (name "unconnected-(U$16-TX-PadP$18)") (class "Default")
      (node (ref "U$16") (pin "P$18") (pinfunction "TX_P$18") (pintype "bidirectional"))
    )
    (net (code "73") (name "unconnected-(U$16-VIN-PadP$15)") (class "Default")
      (node (ref "U$16") (pin "P$15") (pinfunction "VIN_P$15") (pintype "bidirectional"))
    )
    (net (code "74") (name "unconnected-(U$16-VU-PadP$3)") (class "Default")
      (node (ref "U$16") (pin "P$3") (pinfunction "VU_P$3") (pintype "bidirectional"))
    )
    (net (code "75") (name "unconnected-(U$17-1-PadP$1)") (class "Default")
      (node (ref "U$17") (pin "P$1") (pinfunction "1_P$1") (pintype "bidirectional"))
    )
  )
)
